# source_eagle.net
KiCad netlist of a schematic drawn in EAGLE
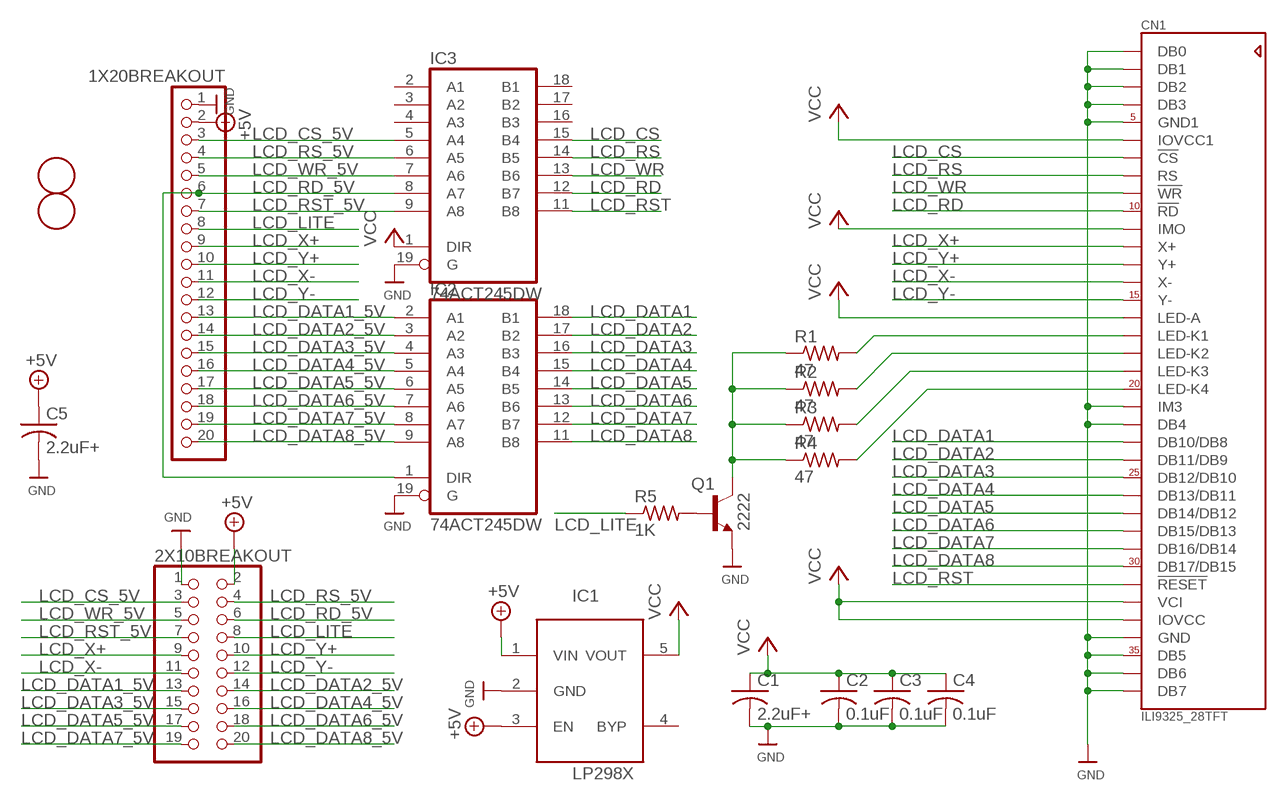
[diagram p0: schematic, sheet 1]

(export (version "E")
  (design (tool "Eeschema 10.0.6"))
  (components
    (comp (ref "1X20BREAKOUT")
      (value "PINHD-1X20")
      (footprint "eagle-import:1X20")
      (libsource (lib "eagle-import") (part "PINHD-1X20"))
    )
    (comp (ref "2X10BREAKOUT")
      (value "PINHD-2X10")
      (footprint "eagle-import:2X10")
      (libsource (lib "eagle-import") (part "PINHD-2X10"))
    )
    (comp (ref "C1")
      (value "2.2uF+")
      (footprint "eagle-import:C0805K")
      (libsource (lib "eagle-import") (part "C-USC0805K"))
    )
    (comp (ref "C2")
      (value "0.1uF")
      (footprint "eagle-import:C0805K")
      (libsource (lib "eagle-import") (part "C-USC0805K"))
    )
    (comp (ref "C3")
      (value "0.1uF")
      (footprint "eagle-import:C0805K")
      (libsource (lib "eagle-import") (part "C-USC0805K"))
    )
    (comp (ref "C4")
      (value "0.1uF")
      (footprint "eagle-import:C0805K")
      (libsource (lib "eagle-import") (part "C-USC0805K"))
    )
    (comp (ref "C5")
      (value "2.2uF+")
      (footprint "eagle-import:C0805K")
      (libsource (lib "eagle-import") (part "C-USC0805K"))
    )
    (comp (ref "CN1")
      (value "ILI9325_28TFT")
      (footprint "eagle-import:ILI9325_28INCH_TS")
      (libsource (lib "eagle-import") (part "ILI9325_LCD1.0MM"))
    )
    (comp (ref "IC1")
      (value "LP298XS")
      (footprint "eagle-import:SOT23-5L")
      (libsource (lib "eagle-import") (part "LP298XS"))
    )
    (comp (ref "IC2")
      (value "74ACT245DW")
      (footprint "eagle-import:SO20W")
      (libsource (lib "eagle-import") (part "74245DWACT"))
    )
    (comp (ref "IC3")
      (value "74ACT245DW")
      (footprint "eagle-import:SO20W")
      (libsource (lib "eagle-import") (part "74245DWACT"))
    )
    (comp (ref "Q1")
      (value "2222")
      (footprint "eagle-import:SOT23-BEC")
      (libsource (lib "eagle-import") (part "-NPN-SOT23-BECMMBT2222ALT1"))
    )
    (comp (ref "R1")
      (value "47")
      (footprint "eagle-import:R0805")
      (libsource (lib "eagle-import") (part "R-US_R0805"))
    )
    (comp (ref "R2")
      (value "47")
      (footprint "eagle-import:R0805")
      (libsource (lib "eagle-import") (part "R-US_R0805"))
    )
    (comp (ref "R3")
      (value "47")
      (footprint "eagle-import:R0805")
      (libsource (lib "eagle-import") (part "R-US_R0805"))
    )
    (comp (ref "R4")
      (value "47")
      (footprint "eagle-import:R0805")
      (libsource (lib "eagle-import") (part "R-US_R0805"))
    )
    (comp (ref "R5")
      (value "1K")
      (footprint "eagle-import:R0805")
      (libsource (lib "eagle-import") (part "R-US_R0805"))
    )
    (comp (ref "U$9")
      (value "FIDUCIAL")
      (footprint "eagle-import:FIDUCIAL_1MM")
      (libsource (lib "eagle-import") (part "FIDUCIAL"))
    )
    (comp (ref "U$11")
      (value "FIDUCIAL")
      (footprint "eagle-import:FIDUCIAL_1MM")
      (libsource (lib "eagle-import") (part "FIDUCIAL"))
    )
  )
  (nets
    (net (code "1") (name "+5V") (class "Default")
      (node (ref "1X20BREAKOUT") (pin "2") (pinfunction "2_2") (pintype "passive"))
      (node (ref "2X10BREAKOUT") (pin "2") (pinfunction "2_2") (pintype "passive"))
      (node (ref "C5") (pin "1") (pinfunction "1_1") (pintype "passive"))
      (node (ref "IC1") (pin "1") (pinfunction "VIN_1") (pintype "bidirectional"))
      (node (ref "IC1") (pin "3") (pinfunction "EN_3") (pintype "bidirectional"))
    )
    (net (code "2") (name "/LCD_CS") (class "Default")
      (node (ref "CN1") (pin "7") (pinfunction "~{CS}_7") (pintype "passive"))
      (node (ref "IC3") (pin "15") (pinfunction "B4_15") (pintype "bidirectional"))
    )
    (net (code "3") (name "/LCD_CS_5V") (class "Default")
      (node (ref "1X20BREAKOUT") (pin "3") (pinfunction "3_3") (pintype "passive"))
      (node (ref "2X10BREAKOUT") (pin "3") (pinfunction "3_3") (pintype "passive"))
      (node (ref "IC3") (pin "5") (pinfunction "A4_5") (pintype "bidirectional"))
    )
    (net (code "4") (name "/LCD_DATA1") (class "Default")
      (node (ref "CN1") (pin "23") (pinfunction "DB10/DB8_23") (pintype "passive"))
      (node (ref "IC2") (pin "18") (pinfunction "B1_18") (pintype "bidirectional"))
    )
    (net (code "5") (name "/LCD_DATA1_5V") (class "Default")
      (node (ref "1X20BREAKOUT") (pin "13") (pinfunction "13_13") (pintype "passive"))
      (node (ref "2X10BREAKOUT") (pin "13") (pinfunction "13_13") (pintype "passive"))
      (node (ref "IC2") (pin "2") (pinfunction "A1_2") (pintype "bidirectional"))
    )
    (net (code "6") (name "/LCD_DATA2") (class "Default")
      (node (ref "CN1") (pin "24") (pinfunction "DB11/DB9_24") (pintype "passive"))
      (node (ref "IC2") (pin "17") (pinfunction "B2_17") (pintype "bidirectional"))
    )
    (net (code "7") (name "/LCD_DATA2_5V") (class "Default")
      (node (ref "1X20BREAKOUT") (pin "14") (pinfunction "14_14") (pintype "passive"))
      (node (ref "2X10BREAKOUT") (pin "14") (pinfunction "14_14") (pintype "passive"))
      (node (ref "IC2") (pin "3") (pinfunction "A2_3") (pintype "bidirectional"))
    )
    (net (code "8") (name "/LCD_DATA3") (class "Default")
      (node (ref "CN1") (pin "25") (pinfunction "DB12/DB10_25") (pintype "passive"))
      (node (ref "IC2") (pin "16") (pinfunction "B3_16") (pintype "bidirectional"))
    )
    (net (code "9") (name "/LCD_DATA3_5V") (class "Default")
      (node (ref "1X20BREAKOUT") (pin "15") (pinfunction "15_15") (pintype "passive"))
      (node (ref "2X10BREAKOUT") (pin "15") (pinfunction "15_15") (pintype "passive"))
      (node (ref "IC2") (pin "4") (pinfunction "A3_4") (pintype "bidirectional"))
    )
    (net (code "10") (name "/LCD_DATA4") (class "Default")
      (node (ref "CN1") (pin "26") (pinfunction "DB13/DB11_26") (pintype "passive"))
      (node (ref "IC2") (pin "15") (pinfunction "B4_15") (pintype "bidirectional"))
    )
    (net (code "11") (name "/LCD_DATA4_5V") (class "Default")
      (node (ref "1X20BREAKOUT") (pin "16") (pinfunction "16_16") (pintype "passive"))
      (node (ref "2X10BREAKOUT") (pin "16") (pinfunction "16_16") (pintype "passive"))
      (node (ref "IC2") (pin "5") (pinfunction "A4_5") (pintype "bidirectional"))
    )
    (net (code "12") (name "/LCD_DATA5") (class "Default")
      (node (ref "CN1") (pin "27") (pinfunction "DB14/DB12_27") (pintype "passive"))
      (node (ref "IC2") (pin "14") (pinfunction "B5_14") (pintype "bidirectional"))
    )
    (net (code "13") (name "/LCD_DATA5_5V") (class "Default")
      (node (ref "1X20BREAKOUT") (pin "17") (pinfunction "17_17") (pintype "passive"))
      (node (ref "2X10BREAKOUT") (pin "17") (pinfunction "17_17") (pintype "passive"))
      (node (ref "IC2") (pin "6") (pinfunction "A5_6") (pintype "bidirectional"))
    )
    (net (code "14") (name "/LCD_DATA6") (class "Default")
      (node (ref "CN1") (pin "28") (pinfunction "DB15/DB13_28") (pintype "passive"))
      (node (ref "IC2") (pin "13") (pinfunction "B6_13") (pintype "bidirectional"))
    )
    (net (code "15") (name "/LCD_DATA6_5V") (class "Default")
      (node (ref "1X20BREAKOUT") (pin "18") (pinfunction "18_18") (pintype "passive"))
      (node (ref "2X10BREAKOUT") (pin "18") (pinfunction "18_18") (pintype "passive"))
      (node (ref "IC2") (pin "7") (pinfunction "A6_7") (pintype "bidirectional"))
    )
    (net (code "16") (name "/LCD_DATA7") (class "Default")
      (node (ref "CN1") (pin "29") (pinfunction "DB16/DB14_29") (pintype "passive"))
      (node (ref "IC2") (pin "12") (pinfunction "B7_12") (pintype "bidirectional"))
    )
    (net (code "17") (name "/LCD_DATA7_5V") (class "Default")
      (node (ref "1X20BREAKOUT") (pin "19") (pinfunction "19_19") (pintype "passive"))
      (node (ref "2X10BREAKOUT") (pin "19") (pinfunction "19_19") (pintype "passive"))
      (node (ref "IC2") (pin "8") (pinfunction "A7_8") (pintype "bidirectional"))
    )
    (net (code "18") (name "/LCD_DATA8") (class "Default")
      (node (ref "CN1") (pin "30") (pinfunction "DB17/DB15_30") (pintype "passive"))
      (node (ref "IC2") (pin "11") (pinfunction "B8_11") (pintype "bidirectional"))
    )
    (net (code "19") (name "/LCD_DATA8_5V") (class "Default")
      (node (ref "1X20BREAKOUT") (pin "20") (pinfunction "20_20") (pintype "passive"))
      (node (ref "2X10BREAKOUT") (pin "20") (pinfunction "20_20") (pintype "passive"))
      (node (ref "IC2") (pin "9") (pinfunction "A8_9") (pintype "bidirectional"))
    )
    (net (code "20") (name "/LCD_LITE") (class "Default")
      (node (ref "1X20BREAKOUT") (pin "8") (pinfunction "8_8") (pintype "passive"))
      (node (ref "2X10BREAKOUT") (pin "8") (pinfunction "8_8") (pintype "passive"))
      (node (ref "R5") (pin "1") (pinfunction "1_1") (pintype "passive"))
    )
    (net (code "21") (name "/LCD_RD") (class "Default")
      (node (ref "CN1") (pin "10") (pinfunction "~{RD}_10") (pintype "passive"))
      (node (ref "IC3") (pin "12") (pinfunction "B7_12") (pintype "bidirectional"))
    )
    (net (code "22") (name "/LCD_RD_5V") (class "Default")
      (node (ref "1X20BREAKOUT") (pin "6") (pinfunction "6_6") (pintype "passive"))
      (node (ref "2X10BREAKOUT") (pin "6") (pinfunction "6_6") (pintype "passive"))
      (node (ref "IC2") (pin "1") (pinfunction "DIR_1") (pintype "input"))
      (node (ref "IC3") (pin "8") (pinfunction "A7_8") (pintype "bidirectional"))
    )
    (net (code "23") (name "/LCD_RS") (class "Default")
      (node (ref "CN1") (pin "8") (pinfunction "RS_8") (pintype "passive"))
      (node (ref "IC3") (pin "14") (pinfunction "B5_14") (pintype "bidirectional"))
    )
    (net (code "24") (name "/LCD_RST") (class "Default")
      (node (ref "CN1") (pin "31") (pinfunction "~{RESET}_31") (pintype "passive"))
      (node (ref "IC3") (pin "11") (pinfunction "B8_11") (pintype "bidirectional"))
    )
    (net (code "25") (name "/LCD_RST_5V") (class "Default")
      (node (ref "1X20BREAKOUT") (pin "7") (pinfunction "7_7") (pintype "passive"))
      (node (ref "2X10BREAKOUT") (pin "7") (pinfunction "7_7") (pintype "passive"))
      (node (ref "IC3") (pin "9") (pinfunction "A8_9") (pintype "bidirectional"))
    )
    (net (code "26") (name "/LCD_RS_5V") (class "Default")
      (node (ref "1X20BREAKOUT") (pin "4") (pinfunction "4_4") (pintype "passive"))
      (node (ref "2X10BREAKOUT") (pin "4") (pinfunction "4_4") (pintype "passive"))
      (node (ref "IC3") (pin "6") (pinfunction "A5_6") (pintype "bidirectional"))
    )
    (net (code "27") (name "/LCD_WR") (class "Default")
      (node (ref "CN1") (pin "9") (pinfunction "~{WR}_9") (pintype "passive"))
      (node (ref "IC3") (pin "13") (pinfunction "B6_13") (pintype "bidirectional"))
    )
    (net (code "28") (name "/LCD_WR_5V") (class "Default")
      (node (ref "1X20BREAKOUT") (pin "5") (pinfunction "5_5") (pintype "passive"))
      (node (ref "2X10BREAKOUT") (pin "5") (pinfunction "5_5") (pintype "passive"))
      (node (ref "IC3") (pin "7") (pinfunction "A6_7") (pintype "bidirectional"))
    )
    (net (code "29") (name "/LCD_X+") (class "Default")
      (node (ref "1X20BREAKOUT") (pin "9") (pinfunction "9_9") (pintype "passive"))
      (node (ref "2X10BREAKOUT") (pin "9") (pinfunction "9_9") (pintype "passive"))
      (node (ref "CN1") (pin "12") (pinfunction "X+_12") (pintype "passive"))
    )
    (net (code "30") (name "/LCD_X-") (class "Default")
      (node (ref "1X20BREAKOUT") (pin "11") (pinfunction "11_11") (pintype "passive"))
      (node (ref "2X10BREAKOUT") (pin "11") (pinfunction "11_11") (pintype "passive"))
      (node (ref "CN1") (pin "14") (pinfunction "X-_14") (pintype "passive"))
    )
    (net (code "31") (name "/LCD_Y+") (class "Default")
      (node (ref "1X20BREAKOUT") (pin "10") (pinfunction "10_10") (pintype "passive"))
      (node (ref "2X10BREAKOUT") (pin "10") (pinfunction "10_10") (pintype "passive"))
      (node (ref "CN1") (pin "13") (pinfunction "Y+_13") (pintype "passive"))
    )
    (net (code "32") (name "/LCD_Y-") (class "Default")
      (node (ref "1X20BREAKOUT") (pin "12") (pinfunction "12_12") (pintype "passive"))
      (node (ref "2X10BREAKOUT") (pin "12") (pinfunction "12_12") (pintype "passive"))
      (node (ref "CN1") (pin "15") (pinfunction "Y-_15") (pintype "passive"))
    )
    (net (code "33") (name "GND") (class "Default")
      (node (ref "1X20BREAKOUT") (pin "1") (pinfunction "1_1") (pintype "passive"))
      (node (ref "2X10BREAKOUT") (pin "1") (pinfunction "1_1") (pintype "passive"))
      (node (ref "C1") (pin "2") (pinfunction "2_2") (pintype "passive"))
      (node (ref "C2") (pin "2") (pinfunction "2_2") (pintype "passive"))
      (node (ref "C3") (pin "2") (pinfunction "2_2") (pintype "passive"))
      (node (ref "C4") (pin "2") (pinfunction "2_2") (pintype "passive"))
      (node (ref "C5") (pin "2") (pinfunction "2_2") (pintype "passive"))
      (node (ref "CN1") (pin "1") (pinfunction "DB0_1") (pintype "passive"))
      (node (ref "CN1") (pin "2") (pinfunction "DB1_2") (pintype "passive"))
      (node (ref "CN1") (pin "21") (pinfunction "IM3_21") (pintype "passive"))
      (node (ref "CN1") (pin "22") (pinfunction "DB4_22") (pintype "passive"))
      (node (ref "CN1") (pin "3") (pinfunction "DB2_3") (pintype "passive"))
      (node (ref "CN1") (pin "34") (pinfunction "GND_34") (pintype "power_in"))
      (node (ref "CN1") (pin "35") (pinfunction "DB5_35") (pintype "passive"))
      (node (ref "CN1") (pin "36") (pinfunction "DB6_36") (pintype "passive"))
      (node (ref "CN1") (pin "37") (pinfunction "DB7_37") (pintype "passive"))
      (node (ref "CN1") (pin "4") (pinfunction "DB3_4") (pintype "passive"))
      (node (ref "CN1") (pin "5") (pinfunction "GND1_5") (pintype "power_in"))
      (node (ref "IC1") (pin "2") (pinfunction "GND_2") (pintype "bidirectional"))
      (node (ref "IC2") (pin "19") (pinfunction "G_19") (pintype "input"))
      (node (ref "IC3") (pin "19") (pinfunction "G_19") (pintype "input"))
      (node (ref "Q1") (pin "E") (pinfunction "E_E") (pintype "passive"))
    )
    (net (code "34") (name "Net-(CN1-LED-K1)") (class "Default")
      (node (ref "CN1") (pin "17") (pinfunction "LED-K1_17") (pintype "passive"))
      (node (ref "R1") (pin "2") (pinfunction "2_2") (pintype "passive"))
    )
    (net (code "35") (name "Net-(CN1-LED-K2)") (class "Default")
      (node (ref "CN1") (pin "18") (pinfunction "LED-K2_18") (pintype "passive"))
      (node (ref "R2") (pin "2") (pinfunction "2_2") (pintype "passive"))
    )
    (net (code "36") (name "Net-(CN1-LED-K3)") (class "Default")
      (node (ref "CN1") (pin "19") (pinfunction "LED-K3_19") (pintype "passive"))
      (node (ref "R3") (pin "2") (pinfunction "2_2") (pintype "passive"))
    )
    (net (code "37") (name "Net-(CN1-LED-K4)") (class "Default")
      (node (ref "CN1") (pin "20") (pinfunction "LED-K4_20") (pintype "passive"))
      (node (ref "R4") (pin "2") (pinfunction "2_2") (pintype "passive"))
    )
    (net (code "38") (name "Net-(Q1-PadB)") (class "Default")
      (node (ref "Q1") (pin "B") (pinfunction "B_B") (pintype "passive"))
      (node (ref "R5") (pin "2") (pinfunction "2_2") (pintype "passive"))
    )
    (net (code "39") (name "Net-(Q1-PadC)") (class "Default")
      (node (ref "Q1") (pin "C") (pinfunction "C_C") (pintype "passive"))
      (node (ref "R1") (pin "1") (pinfunction "1_1") (pintype "passive"))
      (node (ref "R2") (pin "1") (pinfunction "1_1") (pintype "passive"))
      (node (ref "R3") (pin "1") (pinfunction "1_1") (pintype "passive"))
      (node (ref "R4") (pin "1") (pinfunction "1_1") (pintype "passive"))
    )
    (net (code "40") (name "VCC") (class "Default")
      (node (ref "C1") (pin "1") (pinfunction "1_1") (pintype "passive"))
      (node (ref "C2") (pin "1") (pinfunction "1_1") (pintype "passive"))
      (node (ref "C3") (pin "1") (pinfunction "1_1") (pintype "passive"))
      (node (ref "C4") (pin "1") (pinfunction "1_1") (pintype "passive"))
      (node (ref "CN1") (pin "11") (pinfunction "IMO_11") (pintype "passive"))
      (node (ref "CN1") (pin "16") (pinfunction "LED-A_16") (pintype "passive"))
      (node (ref "CN1") (pin "32") (pinfunction "VCI_32") (pintype "power_in"))
      (node (ref "CN1") (pin "33") (pinfunction "IOVCC_33") (pintype "power_in"))
      (node (ref "CN1") (pin "6") (pinfunction "IOVCC1_6") (pintype "power_in"))
      (node (ref "IC1") (pin "5") (pinfunction "VOUT_5") (pintype "bidirectional"))
      (node (ref "IC3") (pin "1") (pinfunction "DIR_1") (pintype "input"))
    )
    (net (code "41") (name "unconnected-(IC1-BYP-Pad4)") (class "Default")
      (node (ref "IC1") (pin "4") (pinfunction "BYP_4") (pintype "bidirectional"))
    )
    (net (code "42") (name "unconnected-(IC3A-A1-Pad2)") (class "Default")
      (node (ref "IC3") (pin "2") (pinfunction "A1_2") (pintype "bidirectional"))
    )
    (net (code "43") (name "unconnected-(IC3A-A2-Pad3)") (class "Default")
      (node (ref "IC3") (pin "3") (pinfunction "A2_3") (pintype "bidirectional"))
    )
    (net (code "44") (name "unconnected-(IC3A-A3-Pad4)") (class "Default")
      (node (ref "IC3") (pin "4") (pinfunction "A3_4") (pintype "bidirectional"))
    )
    (net (code "45") (name "unconnected-(IC3A-B1-Pad18)") (class "Default")
      (node (ref "IC3") (pin "18") (pinfunction "B1_18") (pintype "bidirectional"))
    )
    (net (code "46") (name "unconnected-(IC3A-B2-Pad17)") (class "Default")
      (node (ref "IC3") (pin "17") (pinfunction "B2_17") (pintype "bidirectional"))
    )
    (net (code "47") (name "unconnected-(IC3A-B3-Pad16)") (class "Default")
      (node (ref "IC3") (pin "16") (pinfunction "B3_16") (pintype "bidirectional"))
    )
  )
)
